# Main.net
KiCad netlist of a schematic drawn in Altium Designer
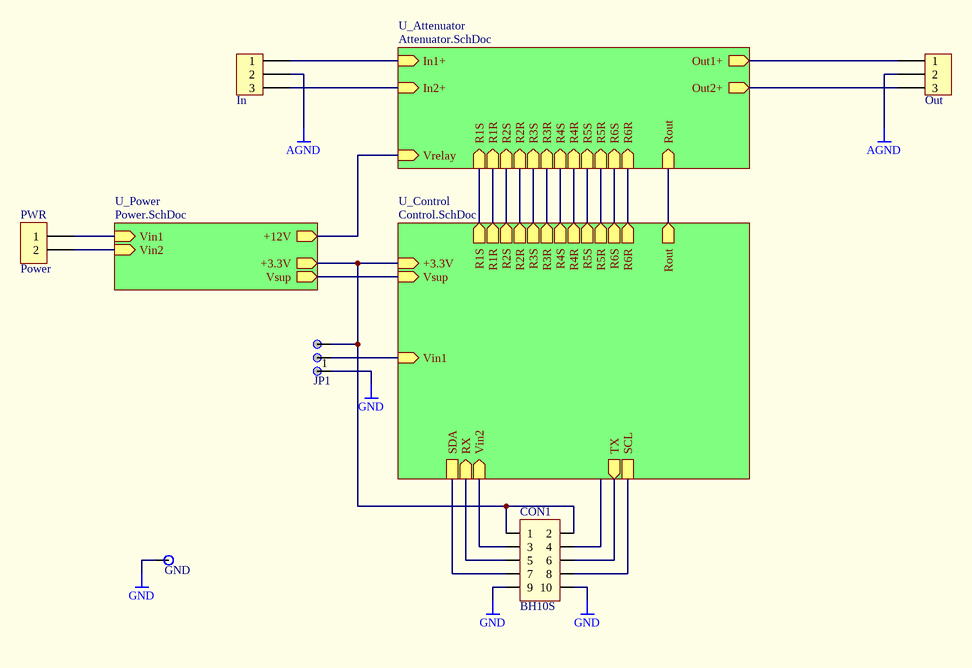
[diagram p0: Main.SchDoc]

(export (version "E")
  (design (tool "Eeschema 10.0.6"))
  (components
    (comp (ref "CON1")
      (value "BH10S")
      (footprint "BH10S")
      (description "BH10S-side mounted")
      (libsource (lib "MainSchlib") (part "CON2x5"))
    )
    (comp (ref "GND") (value "TESTPAD") (footprint "MISC_PAD-36/65") (libsource (lib "*") (part "TESTPAD")))
    (comp (ref "In")
      (value "CON3")
      (footprint "CON_WS03S")
      (description "Connector")
      (libsource (lib "") (part "CON3_1"))
    )
    (comp (ref "JP1") (value "Jumper, 3pin") (footprint "JP3") (libsource (lib "*") (part "JP3")))
    (comp (ref "Out")
      (value "CON3")
      (footprint "CON_WS03S")
      (description "Connector")
      (libsource (lib "*") (part "CON3"))
    )
    (comp (ref "PWR")
      (value "Power")
      (footprint "CONN_TOP_2P")
      (description "Connector")
      (libsource (lib "*") (part "CON2"))
    )
  )
  (nets
    (net (code "1") (name "/+3.3V") (class "Default")
      (node (ref "CON1") (pin "1") (pinfunction "1_1") (pintype "passive"))
      (node (ref "CON1") (pin "2") (pinfunction "2_2") (pintype "passive"))
      (node (ref "JP1") (pin "3") (pinfunction "3_3") (pintype "passive"))
    )
    (net (code "3") (name "/In1+") (class "Default")
      (node (ref "In") (pin "1") (pinfunction "1_1") (pintype "passive"))
    )
    (net (code "4") (name "/In2+") (class "Default")
      (node (ref "In") (pin "3") (pinfunction "3_3") (pintype "passive"))
    )
    (net (code "5") (name "/Out1+") (class "Default")
      (node (ref "Out") (pin "1") (pinfunction "1_1") (pintype "passive"))
    )
    (net (code "6") (name "/Out2+") (class "Default")
      (node (ref "Out") (pin "3") (pinfunction "3_3") (pintype "passive"))
    )
    (net (code "19") (name "/RX") (class "Default")
      (node (ref "CON1") (pin "5") (pinfunction "5_5") (pintype "passive"))
    )
    (net (code "21") (name "/SCL") (class "Default")
      (node (ref "CON1") (pin "8") (pinfunction "8_8") (pintype "passive"))
    )
    (net (code "22") (name "/SDA") (class "Default")
      (node (ref "CON1") (pin "7") (pinfunction "7_7") (pintype "passive"))
    )
    (net (code "23") (name "/TX") (class "Default")
      (node (ref "CON1") (pin "6") (pinfunction "6_6") (pintype "passive"))
    )
    (net (code "24") (name "/Vin1") (class "Default")
      (node (ref "PWR") (pin "1") (pinfunction "1_1") (pintype "passive"))
    )
    (net (code "25") (name "/Vin1_1") (class "Default")
      (node (ref "JP1") (pin "2") (pinfunction "2_2") (pintype "passive"))
    )
    (net (code "26") (name "/Vin2") (class "Default")
      (node (ref "PWR") (pin "2") (pinfunction "2_2") (pintype "passive"))
    )
    (net (code "27") (name "/Vin2_1") (class "Default")
      (node (ref "CON1") (pin "3") (pinfunction "3_3") (pintype "passive"))
    )
    (net (code "29") (name "AGND") (class "Default")
      (node (ref "In") (pin "2") (pinfunction "2_2") (pintype "passive"))
      (node (ref "Out") (pin "2") (pinfunction "2_2") (pintype "passive"))
    )
    (net (code "30") (name "GND") (class "Default")
      (node (ref "CON1") (pin "10") (pinfunction "10_10") (pintype "passive"))
      (node (ref "CON1") (pin "9") (pinfunction "9_9") (pintype "passive"))
      (node (ref "GND") (pin "1") (pinfunction "1_1") (pintype "passive"))
      (node (ref "JP1") (pin "1") (pinfunction "1_1") (pintype "passive"))
    )
    (net (code "31") (name "unconnected-(CON1-Pad4)") (class "Default")
      (node (ref "CON1") (pin "4") (pinfunction "4_4") (pintype "passive"))
    )
  )
)
